# umodular_pot16.net
KiCad netlist of a schematic drawn in EAGLE
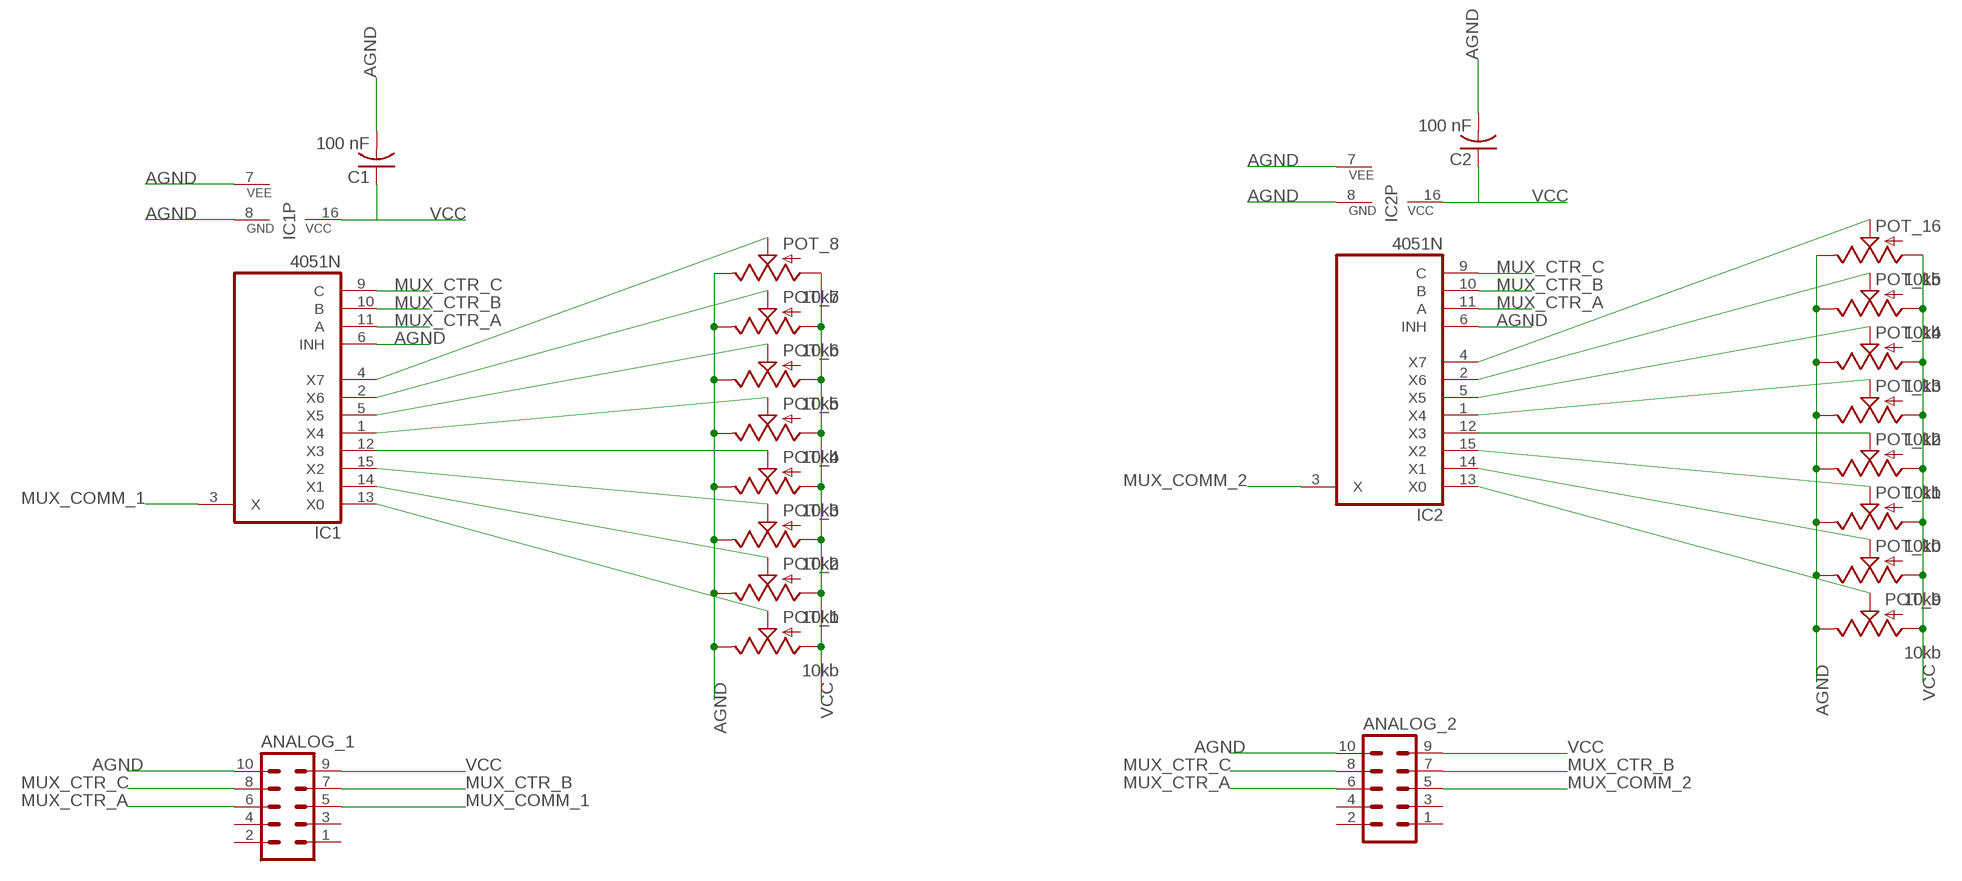
[diagram p0: schematic, sheet 1]

(export (version "E")
  (design (tool "Eeschema 10.0.6"))
  (components
    (comp (ref "ANALOG_1")
      (value "MA05-2")
      (footprint "eagle-import:MA05-2")
      (libsource (lib "eagle-import") (part "MA05-2"))
    )
    (comp (ref "ANALOG_2")
      (value "MA05-2")
      (footprint "eagle-import:MA05-2")
      (libsource (lib "eagle-import") (part "MA05-2"))
    )
    (comp (ref "C1")
      (value "100 nF")
      (footprint "eagle-import:C050-024X044")
      (libsource (lib "eagle-import") (part "C-US050-024X044"))
    )
    (comp (ref "C2")
      (value "100 nF")
      (footprint "eagle-import:C050-024X044")
      (libsource (lib "eagle-import") (part "C-US050-024X044"))
    )
    (comp (ref "IC1")
      (value "4051N")
      (footprint "eagle-import:DIL16")
      (libsource (lib "eagle-import") (part "4051N"))
    )
    (comp (ref "IC2")
      (value "4051N")
      (footprint "eagle-import:DIL16")
      (libsource (lib "eagle-import") (part "4051N"))
    )
    (comp (ref "POT_1")
      (value "10kb")
      (footprint "eagle-import:ALPS_POT")
      (libsource (lib "eagle-import") (part "POT"))
    )
    (comp (ref "POT_2")
      (value "10kb")
      (footprint "eagle-import:ALPS_POT")
      (libsource (lib "eagle-import") (part "POT"))
    )
    (comp (ref "POT_3")
      (value "10kb")
      (footprint "eagle-import:ALPS_POT")
      (libsource (lib "eagle-import") (part "POT"))
    )
    (comp (ref "POT_4")
      (value "10kb")
      (footprint "eagle-import:ALPS_POT")
      (libsource (lib "eagle-import") (part "POT"))
    )
    (comp (ref "POT_5")
      (value "10kb")
      (footprint "eagle-import:ALPS_POT")
      (libsource (lib "eagle-import") (part "POT"))
    )
    (comp (ref "POT_6")
      (value "10kb")
      (footprint "eagle-import:ALPS_POT")
      (libsource (lib "eagle-import") (part "POT"))
    )
    (comp (ref "POT_7")
      (value "10kb")
      (footprint "eagle-import:ALPS_POT")
      (libsource (lib "eagle-import") (part "POT"))
    )
    (comp (ref "POT_8")
      (value "10kb")
      (footprint "eagle-import:ALPS_POT")
      (libsource (lib "eagle-import") (part "POT"))
    )
    (comp (ref "POT_9")
      (value "10kb")
      (footprint "eagle-import:ALPS_POT")
      (libsource (lib "eagle-import") (part "POT"))
    )
    (comp (ref "POT_10")
      (value "10kb")
      (footprint "eagle-import:ALPS_POT")
      (libsource (lib "eagle-import") (part "POT"))
    )
    (comp (ref "POT_11")
      (value "10kb")
      (footprint "eagle-import:ALPS_POT")
      (libsource (lib "eagle-import") (part "POT"))
    )
    (comp (ref "POT_12")
      (value "10kb")
      (footprint "eagle-import:ALPS_POT")
      (libsource (lib "eagle-import") (part "POT"))
    )
    (comp (ref "POT_13")
      (value "10kb")
      (footprint "eagle-import:ALPS_POT")
      (libsource (lib "eagle-import") (part "POT"))
    )
    (comp (ref "POT_14")
      (value "10kb")
      (footprint "eagle-import:ALPS_POT")
      (libsource (lib "eagle-import") (part "POT"))
    )
    (comp (ref "POT_15")
      (value "10kb")
      (footprint "eagle-import:ALPS_POT")
      (libsource (lib "eagle-import") (part "POT"))
    )
    (comp (ref "POT_16")
      (value "10kb")
      (footprint "eagle-import:ALPS_POT")
      (libsource (lib "eagle-import") (part "POT"))
    )
  )
  (nets
    (net (code "1") (name "/AGND") (class "Default")
      (node (ref "ANALOG_1") (pin "10") (pinfunction "10_10") (pintype "passive"))
      (node (ref "ANALOG_2") (pin "10") (pinfunction "10_10") (pintype "passive"))
      (node (ref "C1") (pin "2") (pinfunction "2_2") (pintype "passive"))
      (node (ref "C2") (pin "2") (pinfunction "2_2") (pintype "passive"))
      (node (ref "IC1") (pin "6") (pinfunction "INH_6") (pintype "input"))
      (node (ref "IC1") (pin "7") (pinfunction "VEE_7") (pintype "power_in"))
      (node (ref "IC1") (pin "8") (pinfunction "GND_8") (pintype "power_in"))
      (node (ref "IC2") (pin "6") (pinfunction "INH_6") (pintype "input"))
      (node (ref "IC2") (pin "7") (pinfunction "VEE_7") (pintype "power_in"))
      (node (ref "IC2") (pin "8") (pinfunction "GND_8") (pintype "power_in"))
      (node (ref "POT_1") (pin "P$1") (pinfunction "E_P$1") (pintype "passive"))
      (node (ref "POT_10") (pin "P$1") (pinfunction "E_P$1") (pintype "passive"))
      (node (ref "POT_11") (pin "P$1") (pinfunction "E_P$1") (pintype "passive"))
      (node (ref "POT_12") (pin "P$1") (pinfunction "E_P$1") (pintype "passive"))
      (node (ref "POT_13") (pin "P$1") (pinfunction "E_P$1") (pintype "passive"))
      (node (ref "POT_14") (pin "P$1") (pinfunction "E_P$1") (pintype "passive"))
      (node (ref "POT_15") (pin "P$1") (pinfunction "E_P$1") (pintype "passive"))
      (node (ref "POT_16") (pin "P$1") (pinfunction "E_P$1") (pintype "passive"))
      (node (ref "POT_2") (pin "P$1") (pinfunction "E_P$1") (pintype "passive"))
      (node (ref "POT_3") (pin "P$1") (pinfunction "E_P$1") (pintype "passive"))
      (node (ref "POT_4") (pin "P$1") (pinfunction "E_P$1") (pintype "passive"))
      (node (ref "POT_5") (pin "P$1") (pinfunction "E_P$1") (pintype "passive"))
      (node (ref "POT_6") (pin "P$1") (pinfunction "E_P$1") (pintype "passive"))
      (node (ref "POT_7") (pin "P$1") (pinfunction "E_P$1") (pintype "passive"))
      (node (ref "POT_8") (pin "P$1") (pinfunction "E_P$1") (pintype "passive"))
      (node (ref "POT_9") (pin "P$1") (pinfunction "E_P$1") (pintype "passive"))
    )
    (net (code "2") (name "/MUX_COMM_1") (class "Default")
      (node (ref "ANALOG_1") (pin "5") (pinfunction "5_5") (pintype "passive"))
      (node (ref "IC1") (pin "3") (pinfunction "X_3") (pintype "bidirectional"))
    )
    (net (code "3") (name "/MUX_COMM_2") (class "Default")
      (node (ref "ANALOG_2") (pin "5") (pinfunction "5_5") (pintype "passive"))
      (node (ref "IC2") (pin "3") (pinfunction "X_3") (pintype "bidirectional"))
    )
    (net (code "4") (name "/MUX_CTR_A") (class "Default")
      (node (ref "ANALOG_1") (pin "6") (pinfunction "6_6") (pintype "passive"))
      (node (ref "ANALOG_2") (pin "6") (pinfunction "6_6") (pintype "passive"))
      (node (ref "IC1") (pin "11") (pinfunction "A_11") (pintype "input"))
      (node (ref "IC2") (pin "11") (pinfunction "A_11") (pintype "input"))
    )
    (net (code "5") (name "/MUX_CTR_B") (class "Default")
      (node (ref "ANALOG_1") (pin "7") (pinfunction "7_7") (pintype "passive"))
      (node (ref "ANALOG_2") (pin "7") (pinfunction "7_7") (pintype "passive"))
      (node (ref "IC1") (pin "10") (pinfunction "B_10") (pintype "input"))
      (node (ref "IC2") (pin "10") (pinfunction "B_10") (pintype "input"))
    )
    (net (code "6") (name "/MUX_CTR_C") (class "Default")
      (node (ref "ANALOG_1") (pin "8") (pinfunction "8_8") (pintype "passive"))
      (node (ref "ANALOG_2") (pin "8") (pinfunction "8_8") (pintype "passive"))
      (node (ref "IC1") (pin "9") (pinfunction "C_9") (pintype "input"))
      (node (ref "IC2") (pin "9") (pinfunction "C_9") (pintype "input"))
    )
    (net (code "7") (name "/VCC") (class "Default")
      (node (ref "ANALOG_1") (pin "9") (pinfunction "9_9") (pintype "passive"))
      (node (ref "ANALOG_2") (pin "9") (pinfunction "9_9") (pintype "passive"))
      (node (ref "C1") (pin "1") (pinfunction "1_1") (pintype "passive"))
      (node (ref "C2") (pin "1") (pinfunction "1_1") (pintype "passive"))
      (node (ref "IC1") (pin "16") (pinfunction "VCC_16") (pintype "power_in"))
      (node (ref "IC2") (pin "16") (pinfunction "VCC_16") (pintype "power_in"))
      (node (ref "POT_1") (pin "P$3") (pinfunction "A_P$3") (pintype "passive"))
      (node (ref "POT_10") (pin "P$3") (pinfunction "A_P$3") (pintype "passive"))
      (node (ref "POT_11") (pin "P$3") (pinfunction "A_P$3") (pintype "passive"))
      (node (ref "POT_12") (pin "P$3") (pinfunction "A_P$3") (pintype "passive"))
      (node (ref "POT_13") (pin "P$3") (pinfunction "A_P$3") (pintype "passive"))
      (node (ref "POT_14") (pin "P$3") (pinfunction "A_P$3") (pintype "passive"))
      (node (ref "POT_15") (pin "P$3") (pinfunction "A_P$3") (pintype "passive"))
      (node (ref "POT_16") (pin "P$3") (pinfunction "A_P$3") (pintype "passive"))
      (node (ref "POT_2") (pin "P$3") (pinfunction "A_P$3") (pintype "passive"))
      (node (ref "POT_3") (pin "P$3") (pinfunction "A_P$3") (pintype "passive"))
      (node (ref "POT_4") (pin "P$3") (pinfunction "A_P$3") (pintype "passive"))
      (node (ref "POT_5") (pin "P$3") (pinfunction "A_P$3") (pintype "passive"))
      (node (ref "POT_6") (pin "P$3") (pinfunction "A_P$3") (pintype "passive"))
      (node (ref "POT_7") (pin "P$3") (pinfunction "A_P$3") (pintype "passive"))
      (node (ref "POT_8") (pin "P$3") (pinfunction "A_P$3") (pintype "passive"))
      (node (ref "POT_9") (pin "P$3") (pinfunction "A_P$3") (pintype "passive"))
    )
    (net (code "8") (name "Net-(IC1A-X0)") (class "Default")
      (node (ref "IC1") (pin "13") (pinfunction "X0_13") (pintype "bidirectional"))
      (node (ref "POT_1") (pin "P$2") (pinfunction "S_P$2") (pintype "passive"))
    )
    (net (code "9") (name "Net-(IC1A-X1)") (class "Default")
      (node (ref "IC1") (pin "14") (pinfunction "X1_14") (pintype "bidirectional"))
      (node (ref "POT_2") (pin "P$2") (pinfunction "S_P$2") (pintype "passive"))
    )
    (net (code "10") (name "Net-(IC1A-X2)") (class "Default")
      (node (ref "IC1") (pin "15") (pinfunction "X2_15") (pintype "bidirectional"))
      (node (ref "POT_3") (pin "P$2") (pinfunction "S_P$2") (pintype "passive"))
    )
    (net (code "11") (name "Net-(IC1A-X3)") (class "Default")
      (node (ref "IC1") (pin "12") (pinfunction "X3_12") (pintype "bidirectional"))
      (node (ref "POT_4") (pin "P$2") (pinfunction "S_P$2") (pintype "passive"))
    )
    (net (code "12") (name "Net-(IC1A-X4)") (class "Default")
      (node (ref "IC1") (pin "1") (pinfunction "X4_1") (pintype "bidirectional"))
      (node (ref "POT_5") (pin "P$2") (pinfunction "S_P$2") (pintype "passive"))
    )
    (net (code "13") (name "Net-(IC1A-X5)") (class "Default")
      (node (ref "IC1") (pin "5") (pinfunction "X5_5") (pintype "bidirectional"))
      (node (ref "POT_6") (pin "P$2") (pinfunction "S_P$2") (pintype "passive"))
    )
    (net (code "14") (name "Net-(IC1A-X6)") (class "Default")
      (node (ref "IC1") (pin "2") (pinfunction "X6_2") (pintype "bidirectional"))
      (node (ref "POT_7") (pin "P$2") (pinfunction "S_P$2") (pintype "passive"))
    )
    (net (code "15") (name "Net-(IC1A-X7)") (class "Default")
      (node (ref "IC1") (pin "4") (pinfunction "X7_4") (pintype "bidirectional"))
      (node (ref "POT_8") (pin "P$2") (pinfunction "S_P$2") (pintype "passive"))
    )
    (net (code "16") (name "Net-(IC2A-X0)") (class "Default")
      (node (ref "IC2") (pin "13") (pinfunction "X0_13") (pintype "bidirectional"))
      (node (ref "POT_9") (pin "P$2") (pinfunction "S_P$2") (pintype "passive"))
    )
    (net (code "17") (name "Net-(IC2A-X1)") (class "Default")
      (node (ref "IC2") (pin "14") (pinfunction "X1_14") (pintype "bidirectional"))
      (node (ref "POT_10") (pin "P$2") (pinfunction "S_P$2") (pintype "passive"))
    )
    (net (code "18") (name "Net-(IC2A-X2)") (class "Default")
      (node (ref "IC2") (pin "15") (pinfunction "X2_15") (pintype "bidirectional"))
      (node (ref "POT_11") (pin "P$2") (pinfunction "S_P$2") (pintype "passive"))
    )
    (net (code "19") (name "Net-(IC2A-X3)") (class "Default")
      (node (ref "IC2") (pin "12") (pinfunction "X3_12") (pintype "bidirectional"))
      (node (ref "POT_12") (pin "P$2") (pinfunction "S_P$2") (pintype "passive"))
    )
    (net (code "20") (name "Net-(IC2A-X4)") (class "Default")
      (node (ref "IC2") (pin "1") (pinfunction "X4_1") (pintype "bidirectional"))
      (node (ref "POT_13") (pin "P$2") (pinfunction "S_P$2") (pintype "passive"))
    )
    (net (code "21") (name "Net-(IC2A-X5)") (class "Default")
      (node (ref "IC2") (pin "5") (pinfunction "X5_5") (pintype "bidirectional"))
      (node (ref "POT_14") (pin "P$2") (pinfunction "S_P$2") (pintype "passive"))
    )
    (net (code "22") (name "Net-(IC2A-X6)") (class "Default")
      (node (ref "IC2") (pin "2") (pinfunction "X6_2") (pintype "bidirectional"))
      (node (ref "POT_15") (pin "P$2") (pinfunction "S_P$2") (pintype "passive"))
    )
    (net (code "23") (name "Net-(IC2A-X7)") (class "Default")
      (node (ref "IC2") (pin "4") (pinfunction "X7_4") (pintype "bidirectional"))
      (node (ref "POT_16") (pin "P$2") (pinfunction "S_P$2") (pintype "passive"))
    )
    (net (code "24") (name "unconnected-(ANALOG_1-Pad1)") (class "Default")
      (node (ref "ANALOG_1") (pin "1") (pinfunction "1_1") (pintype "passive"))
    )
    (net (code "25") (name "unconnected-(ANALOG_1-Pad2)") (class "Default")
      (node (ref "ANALOG_1") (pin "2") (pinfunction "2_2") (pintype "passive"))
    )
    (net (code "26") (name "unconnected-(ANALOG_1-Pad3)") (class "Default")
      (node (ref "ANALOG_1") (pin "3") (pinfunction "3_3") (pintype "passive"))
    )
    (net (code "27") (name "unconnected-(ANALOG_1-Pad4)") (class "Default")
      (node (ref "ANALOG_1") (pin "4") (pinfunction "4_4") (pintype "passive"))
    )
    (net (code "28") (name "unconnected-(ANALOG_2-Pad1)") (class "Default")
      (node (ref "ANALOG_2") (pin "1") (pinfunction "1_1") (pintype "passive"))
    )
    (net (code "29") (name "unconnected-(ANALOG_2-Pad2)") (class "Default")
      (node (ref "ANALOG_2") (pin "2") (pinfunction "2_2") (pintype "passive"))
    )
    (net (code "30") (name "unconnected-(ANALOG_2-Pad3)") (class "Default")
      (node (ref "ANALOG_2") (pin "3") (pinfunction "3_3") (pintype "passive"))
    )
    (net (code "31") (name "unconnected-(ANALOG_2-Pad4)") (class "Default")
      (node (ref "ANALOG_2") (pin "4") (pinfunction "4_4") (pintype "passive"))
    )
  )
)
